# omni-ultra-l1.net
KiCad netlist of a schematic drawn in EAGLE
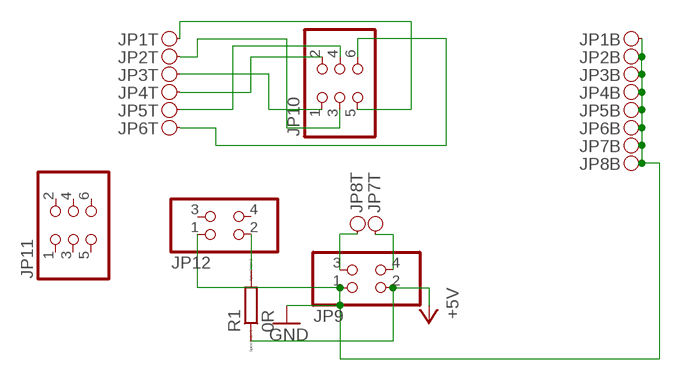
[diagram p0: schematic, sheet 1]

(export (version "E")
  (design (tool "Eeschema 10.0.6"))
  (components
    (comp (ref "JP1")
      (value "PINH2X01")
      (footprint "eagle-import:PINH2X01SMD")
      (libsource (lib "eagle-import") (part "PINH2X01"))
    )
    (comp (ref "JP2")
      (value "PINH2X01")
      (footprint "eagle-import:PINH2X01SMD")
      (libsource (lib "eagle-import") (part "PINH2X01"))
    )
    (comp (ref "JP3")
      (value "PINH2X01")
      (footprint "eagle-import:PINH2X01SMD")
      (libsource (lib "eagle-import") (part "PINH2X01"))
    )
    (comp (ref "JP4")
      (value "PINH2X01")
      (footprint "eagle-import:PINH2X01SMD")
      (libsource (lib "eagle-import") (part "PINH2X01"))
    )
    (comp (ref "JP5")
      (value "PINH2X01")
      (footprint "eagle-import:PINH2X01SMD")
      (libsource (lib "eagle-import") (part "PINH2X01"))
    )
    (comp (ref "JP6")
      (value "PINH2X01")
      (footprint "eagle-import:PINH2X01SMD")
      (libsource (lib "eagle-import") (part "PINH2X01"))
    )
    (comp (ref "JP7")
      (value "PINH2X01")
      (footprint "eagle-import:PINH2X01SMD")
      (libsource (lib "eagle-import") (part "PINH2X01"))
    )
    (comp (ref "JP8")
      (value "PINH2X01")
      (footprint "eagle-import:PINH2X01SMD")
      (libsource (lib "eagle-import") (part "PINH2X01"))
    )
    (comp (ref "JP9")
      (value "PINHD-2X2")
      (footprint "eagle-import:2X02")
      (libsource (lib "eagle-import") (part "PINHD-2X2"))
    )
    (comp (ref "JP10")
      (value "PINHD-2X3")
      (footprint "eagle-import:2X03")
      (libsource (lib "eagle-import") (part "PINHD-2X3"))
    )
    (comp (ref "JP11")
      (value "PINHD-2X3")
      (footprint "eagle-import:2X03")
      (libsource (lib "eagle-import") (part "PINHD-2X3"))
    )
    (comp (ref "JP12")
      (value "PINHD-2X2")
      (footprint "eagle-import:2X02")
      (libsource (lib "eagle-import") (part "PINHD-2X2"))
    )
    (comp (ref "R1")
      (value "0R")
      (footprint "eagle-import:R1206")
      (libsource (lib "eagle-import") (part "RR1206"))
    )
  )
  (nets
    (net (code "1") (name "+5V") (class "Default")
      (node (ref "JP9") (pin "2") (pinfunction "2_2") (pintype "passive"))
      (node (ref "R1") (pin "1") (pinfunction "1_1") (pintype "passive"))
    )
    (net (code "2") (name "GND") (class "Default")
      (node (ref "JP1") (pin "B1") (pinfunction "1_B1") (pintype "passive"))
      (node (ref "JP12") (pin "1") (pinfunction "1_1") (pintype "passive"))
      (node (ref "JP2") (pin "B1") (pinfunction "1_B1") (pintype "passive"))
      (node (ref "JP3") (pin "B1") (pinfunction "1_B1") (pintype "passive"))
      (node (ref "JP4") (pin "B1") (pinfunction "1_B1") (pintype "passive"))
      (node (ref "JP5") (pin "B1") (pinfunction "1_B1") (pintype "passive"))
      (node (ref "JP6") (pin "B1") (pinfunction "1_B1") (pintype "passive"))
      (node (ref "JP7") (pin "B1") (pinfunction "1_B1") (pintype "passive"))
      (node (ref "JP8") (pin "B1") (pinfunction "1_B1") (pintype "passive"))
      (node (ref "JP9") (pin "1") (pinfunction "1_1") (pintype "passive"))
    )
    (net (code "3") (name "Net-(JP1B-1)") (class "Default")
      (node (ref "JP1") (pin "T1") (pinfunction "1_T1") (pintype "passive"))
      (node (ref "JP10") (pin "5") (pinfunction "5_5") (pintype "passive"))
    )
    (net (code "4") (name "Net-(JP2B-1)") (class "Default")
      (node (ref "JP10") (pin "3") (pinfunction "3_3") (pintype "passive"))
      (node (ref "JP2") (pin "T1") (pinfunction "1_T1") (pintype "passive"))
    )
    (net (code "5") (name "Net-(JP3B-1)") (class "Default")
      (node (ref "JP10") (pin "1") (pinfunction "1_1") (pintype "passive"))
      (node (ref "JP3") (pin "T1") (pinfunction "1_T1") (pintype "passive"))
    )
    (net (code "6") (name "Net-(JP4B-1)") (class "Default")
      (node (ref "JP10") (pin "2") (pinfunction "2_2") (pintype "passive"))
      (node (ref "JP4") (pin "T1") (pinfunction "1_T1") (pintype "passive"))
    )
    (net (code "7") (name "Net-(JP5B-1)") (class "Default")
      (node (ref "JP10") (pin "4") (pinfunction "4_4") (pintype "passive"))
      (node (ref "JP5") (pin "T1") (pinfunction "1_T1") (pintype "passive"))
    )
    (net (code "8") (name "Net-(JP6B-1)") (class "Default")
      (node (ref "JP10") (pin "6") (pinfunction "6_6") (pintype "passive"))
      (node (ref "JP6") (pin "T1") (pinfunction "1_T1") (pintype "passive"))
    )
    (net (code "9") (name "Net-(JP7B-1)") (class "Default")
      (node (ref "JP7") (pin "T1") (pinfunction "1_T1") (pintype "passive"))
      (node (ref "JP9") (pin "4") (pinfunction "4_4") (pintype "passive"))
    )
    (net (code "10") (name "Net-(JP8B-1)") (class "Default")
      (node (ref "JP8") (pin "T1") (pinfunction "1_T1") (pintype "passive"))
      (node (ref "JP9") (pin "3") (pinfunction "3_3") (pintype "passive"))
    )
    (net (code "11") (name "Net-(JP12-Pad2)") (class "Default")
      (node (ref "JP12") (pin "2") (pinfunction "2_2") (pintype "passive"))
      (node (ref "R1") (pin "2") (pinfunction "2_2") (pintype "passive"))
    )
    (net (code "12") (name "unconnected-(JP11-Pad1)") (class "Default")
      (node (ref "JP11") (pin "1") (pinfunction "1_1") (pintype "passive"))
    )
    (net (code "13") (name "unconnected-(JP11-Pad2)") (class "Default")
      (node (ref "JP11") (pin "2") (pinfunction "2_2") (pintype "passive"))
    )
    (net (code "14") (name "unconnected-(JP11-Pad3)") (class "Default")
      (node (ref "JP11") (pin "3") (pinfunction "3_3") (pintype "passive"))
    )
    (net (code "15") (name "unconnected-(JP11-Pad4)") (class "Default")
      (node (ref "JP11") (pin "4") (pinfunction "4_4") (pintype "passive"))
    )
    (net (code "16") (name "unconnected-(JP11-Pad5)") (class "Default")
      (node (ref "JP11") (pin "5") (pinfunction "5_5") (pintype "passive"))
    )
    (net (code "17") (name "unconnected-(JP11-Pad6)") (class "Default")
      (node (ref "JP11") (pin "6") (pinfunction "6_6") (pintype "passive"))
    )
    (net (code "18") (name "unconnected-(JP12-Pad3)") (class "Default")
      (node (ref "JP12") (pin "3") (pinfunction "3_3") (pintype "passive"))
    )
    (net (code "19") (name "unconnected-(JP12-Pad4)") (class "Default")
      (node (ref "JP12") (pin "4") (pinfunction "4_4") (pintype "passive"))
    )
  )
)
